# MDC_ESP32.net
KiCad netlist of a schematic drawn in Altium Designer
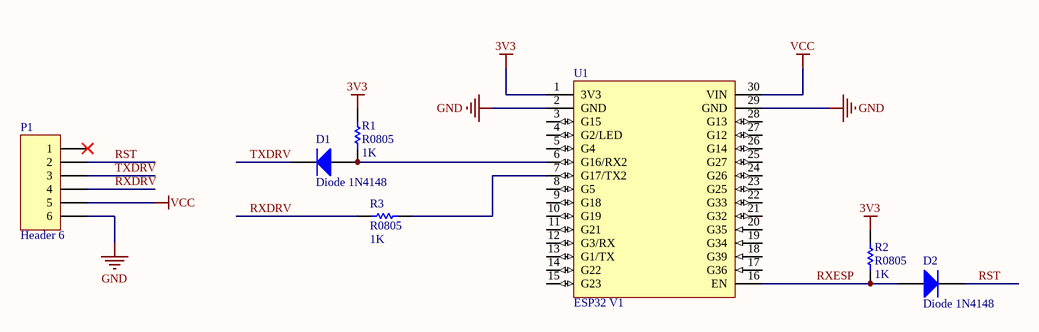
[diagram p0: MDC_ESP32.SchDoc]

(export (version "E")
  (design (tool "Eeschema 10.0.6"))
  (components
    (comp (ref "D1")
      (value "Diode 1N4148")
      (footprint "1N4148SMD")
      (description "1N4148")
      (fields (field (name "PART") "1N4148WTPMSCT") (field (name "PUBLISHER") "Altium Limited"))
      (libsource (lib "PROPIASchlib") (part "Diode 1N4148"))
    )
    (comp (ref "D2")
      (value "Diode 1N4148")
      (footprint "1N4148SMD")
      (description "1N4148")
      (fields (field (name "PART") "1N4148WTPMSCT") (field (name "PUBLISHER") "Altium Limited"))
      (libsource (lib "PROPIASchlib") (part "Diode 1N4148"))
    )
    (comp (ref "P1")
      (value "Header 6")
      (footprint "HDR1X6")
      (description "Header, 6-Pin")
      (fields (field (name "PUBLISHER") "Altium Limited"))
      (libsource (lib "Miscellaneous Connectors") (part "Header 6"))
    )
    (comp (ref "R1")
      (value "R0805")
      (footprint "R0805")
      (description "Semiconductor Resistor")
      (fields
        (field (name "PART") "311-1.0KARCT-ND")
        (field (name "ALTIUM_VALUE") "1K")
        (field (name "PUBLISHER") "Altium Limited")
      )
      (libsource (lib "PROPIASchlib") (part "Res 0805 1K"))
    )
    (comp (ref "R2")
      (value "R0805")
      (footprint "R0805")
      (description "Semiconductor Resistor")
      (fields
        (field (name "PART") "311-1.0KARCT-ND")
        (field (name "ALTIUM_VALUE") "1K")
        (field (name "PUBLISHER") "Altium Limited")
      )
      (libsource (lib "PROPIASchlib") (part "Res 0805 1K"))
    )
    (comp (ref "R3")
      (value "R0805")
      (footprint "R0805")
      (description "Semiconductor Resistor")
      (fields
        (field (name "PART") "311-1.0KARCT-ND")
        (field (name "ALTIUM_VALUE") "1K")
        (field (name "PUBLISHER") "Altium Limited")
      )
      (libsource (lib "PROPIASchlib") (part "Res 0805 1K"))
    )
    (comp (ref "U1")
      (value "ESP32 V1")
      (footprint "ESP32_V1")
      (description "ESP32 V1 Module")
      (libsource (lib "PROPIASchlib") (part "ESP32_V1"))
    )
  )
  (nets
    (net (code "1") (name "/RST") (class "Default")
      (node (ref "D2") (pin "2") (pinfunction "K_2") (pintype "passive"))
      (node (ref "P1") (pin "2") (pinfunction "2_2") (pintype "passive"))
    )
    (net (code "2") (name "/RXDRV") (class "Default")
      (node (ref "P1") (pin "4") (pinfunction "4_4") (pintype "passive"))
      (node (ref "R3") (pin "1") (pinfunction "1_1") (pintype "passive"))
    )
    (net (code "3") (name "/RXESP") (class "Default")
      (node (ref "D2") (pin "1") (pinfunction "A_1") (pintype "passive"))
      (node (ref "R2") (pin "1") (pinfunction "1_1") (pintype "passive"))
      (node (ref "U1") (pin "16") (pinfunction "EN_16") (pintype "passive"))
    )
    (net (code "4") (name "/TXDRV") (class "Default")
      (node (ref "D1") (pin "2") (pinfunction "K_2") (pintype "passive"))
      (node (ref "P1") (pin "3") (pinfunction "3_3") (pintype "passive"))
    )
    (net (code "5") (name "3V3") (class "Default")
      (node (ref "R1") (pin "2") (pinfunction "2_2") (pintype "passive"))
      (node (ref "R2") (pin "2") (pinfunction "2_2") (pintype "passive"))
      (node (ref "U1") (pin "1") (pinfunction "3V3_1") (pintype "power_in"))
    )
    (net (code "6") (name "GND") (class "Default")
      (node (ref "P1") (pin "6") (pinfunction "6_6") (pintype "passive"))
      (node (ref "U1") (pin "2") (pinfunction "GND_2") (pintype "power_in"))
      (node (ref "U1") (pin "29") (pinfunction "GND_29") (pintype "power_in"))
    )
    (net (code "7") (name "Net-(D1-A)") (class "Default")
      (node (ref "D1") (pin "1") (pinfunction "A_1") (pintype "passive"))
      (node (ref "R1") (pin "1") (pinfunction "1_1") (pintype "passive"))
      (node (ref "U1") (pin "6") (pinfunction "G16/RX2_6") (pintype "bidirectional"))
    )
    (net (code "8") (name "Net-(U1-G17{slash}TX2)") (class "Default")
      (node (ref "R3") (pin "2") (pinfunction "2_2") (pintype "passive"))
      (node (ref "U1") (pin "7") (pinfunction "G17/TX2_7") (pintype "bidirectional"))
    )
    (net (code "9") (name "VCC") (class "Default")
      (node (ref "P1") (pin "5") (pinfunction "5_5") (pintype "passive"))
      (node (ref "U1") (pin "30") (pinfunction "VIN_30") (pintype "power_in"))
    )
    (net (code "10") (name "unconnected-(P1-Pad1)") (class "Default")
      (node (ref "P1") (pin "1") (pinfunction "1_1") (pintype "passive+no_connect"))
    )
    (net (code "11") (name "unconnected-(U1-G1{slash}TX-Pad13)") (class "Default")
      (node (ref "U1") (pin "13") (pinfunction "G1/TX_13") (pintype "bidirectional"))
    )
    (net (code "12") (name "unconnected-(U1-G2{slash}LED-Pad4)") (class "Default")
      (node (ref "U1") (pin "4") (pinfunction "G2/LED_4") (pintype "bidirectional"))
    )
    (net (code "13") (name "unconnected-(U1-G3{slash}RX-Pad12)") (class "Default")
      (node (ref "U1") (pin "12") (pinfunction "G3/RX_12") (pintype "bidirectional"))
    )
    (net (code "14") (name "unconnected-(U1-G4-Pad5)") (class "Default")
      (node (ref "U1") (pin "5") (pinfunction "G4_5") (pintype "bidirectional"))
    )
    (net (code "15") (name "unconnected-(U1-G5-Pad8)") (class "Default")
      (node (ref "U1") (pin "8") (pinfunction "G5_8") (pintype "bidirectional"))
    )
    (net (code "16") (name "unconnected-(U1-G12-Pad27)") (class "Default")
      (node (ref "U1") (pin "27") (pinfunction "G12_27") (pintype "bidirectional"))
    )
    (net (code "17") (name "unconnected-(U1-G13-Pad28)") (class "Default")
      (node (ref "U1") (pin "28") (pinfunction "G13_28") (pintype "bidirectional"))
    )
    (net (code "18") (name "unconnected-(U1-G14-Pad26)") (class "Default")
      (node (ref "U1") (pin "26") (pinfunction "G14_26") (pintype "bidirectional"))
    )
    (net (code "19") (name "unconnected-(U1-G15-Pad3)") (class "Default")
      (node (ref "U1") (pin "3") (pinfunction "G15_3") (pintype "bidirectional"))
    )
    (net (code "20") (name "unconnected-(U1-G18-Pad9)") (class "Default")
      (node (ref "U1") (pin "9") (pinfunction "G18_9") (pintype "bidirectional"))
    )
    (net (code "21") (name "unconnected-(U1-G19-Pad10)") (class "Default")
      (node (ref "U1") (pin "10") (pinfunction "G19_10") (pintype "bidirectional"))
    )
    (net (code "22") (name "unconnected-(U1-G21-Pad11)") (class "Default")
      (node (ref "U1") (pin "11") (pinfunction "G21_11") (pintype "bidirectional"))
    )
    (net (code "23") (name "unconnected-(U1-G22-Pad14)") (class "Default")
      (node (ref "U1") (pin "14") (pinfunction "G22_14") (pintype "bidirectional"))
    )
    (net (code "24") (name "unconnected-(U1-G23-Pad15)") (class "Default")
      (node (ref "U1") (pin "15") (pinfunction "G23_15") (pintype "bidirectional"))
    )
    (net (code "25") (name "unconnected-(U1-G25-Pad23)") (class "Default")
      (node (ref "U1") (pin "23") (pinfunction "G25_23") (pintype "bidirectional"))
    )
    (net (code "26") (name "unconnected-(U1-G26-Pad24)") (class "Default")
      (node (ref "U1") (pin "24") (pinfunction "G26_24") (pintype "bidirectional"))
    )
    (net (code "27") (name "unconnected-(U1-G27-Pad25)") (class "Default")
      (node (ref "U1") (pin "25") (pinfunction "G27_25") (pintype "bidirectional"))
    )
    (net (code "28") (name "unconnected-(U1-G32-Pad21)") (class "Default")
      (node (ref "U1") (pin "21") (pinfunction "G32_21") (pintype "bidirectional"))
    )
    (net (code "29") (name "unconnected-(U1-G33-Pad22)") (class "Default")
      (node (ref "U1") (pin "22") (pinfunction "G33_22") (pintype "bidirectional"))
    )
    (net (code "30") (name "unconnected-(U1-G34-Pad19)") (class "Default")
      (node (ref "U1") (pin "19") (pinfunction "G34_19") (pintype "input"))
    )
    (net (code "31") (name "unconnected-(U1-G35-Pad20)") (class "Default")
      (node (ref "U1") (pin "20") (pinfunction "G35_20") (pintype "input"))
    )
    (net (code "32") (name "unconnected-(U1-G36-Pad17)") (class "Default")
      (node (ref "U1") (pin "17") (pinfunction "G36_17") (pintype "input"))
    )
    (net (code "33") (name "unconnected-(U1-G39-Pad18)") (class "Default")
      (node (ref "U1") (pin "18") (pinfunction "G39_18") (pintype "input"))
    )
  )
)
